# SignalOutput.net
KiCad netlist of a schematic drawn in Altium Designer
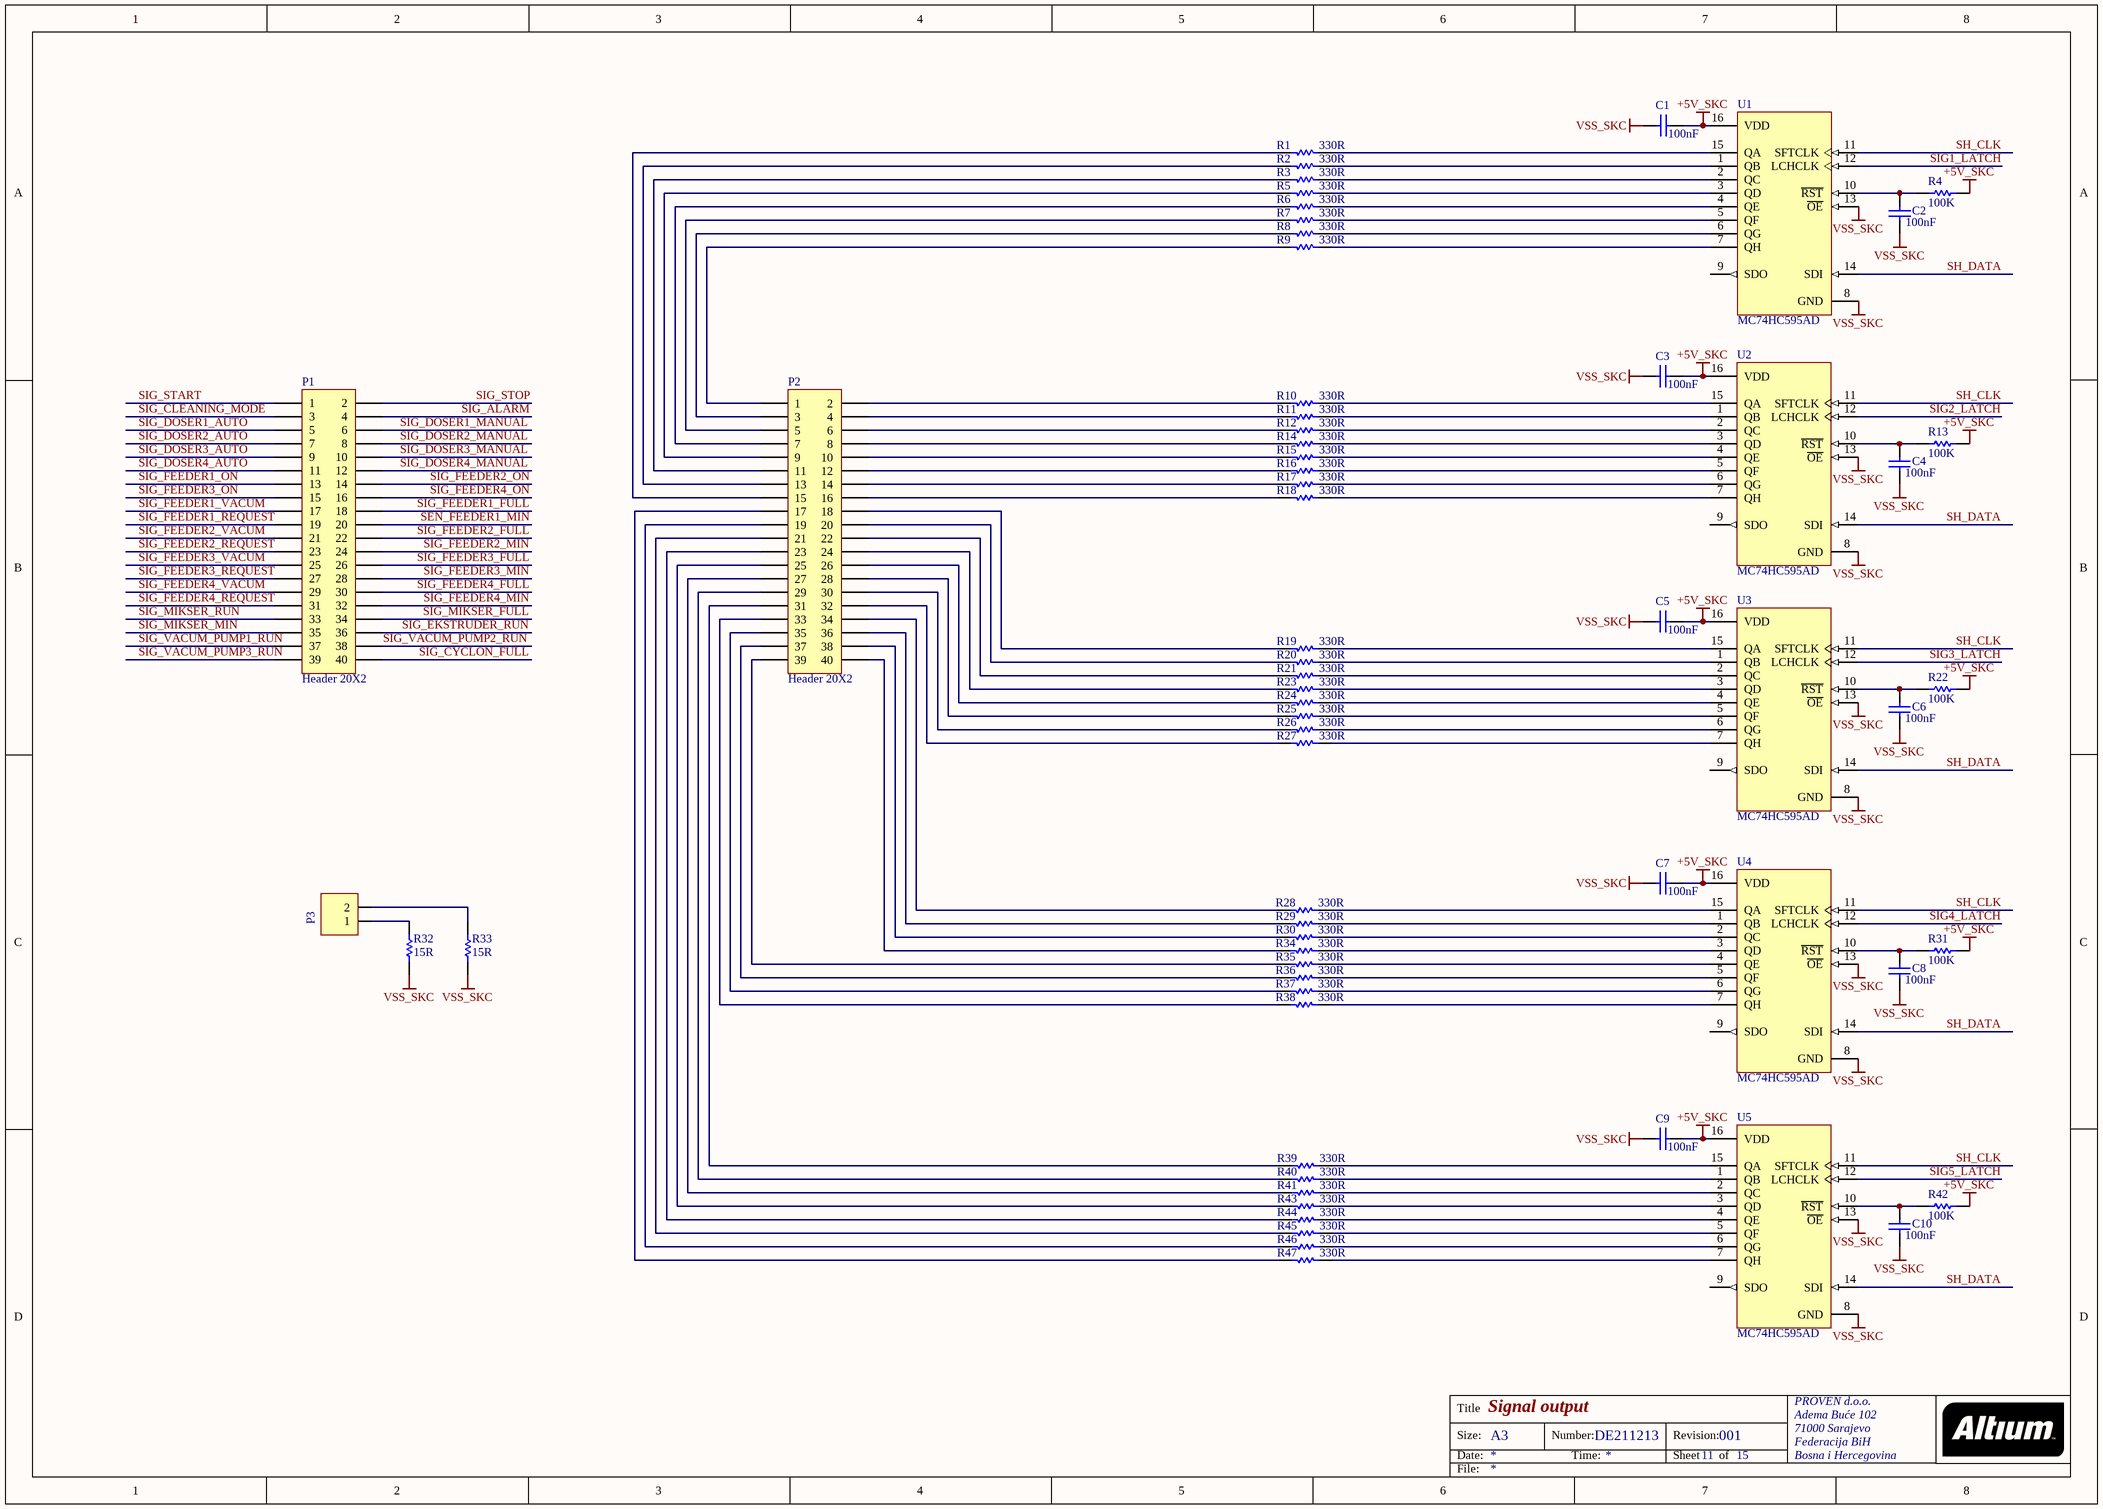
[diagram p0: SignalOutput.SchDoc]

(export (version "E")
  (design (tool "Eeschema 10.0.6"))
  (components
    (comp (ref "C1")
      (value "100nF")
      (footprint "1206")
      (description "Ceramic Chip Capacitor - Standard")
      (fields (field (name "PUBLISHER") "Altium Limited"))
      (libsource (lib "KEMET Chip Capacitor") (part "C1206"))
    )
    (comp (ref "C2")
      (value "100nF")
      (footprint "1206")
      (description "Ceramic Chip Capacitor - Standard")
      (fields (field (name "PUBLISHER") "Altium Limited"))
      (libsource (lib "KEMET Chip Capacitor") (part "C1206"))
    )
    (comp (ref "C3")
      (value "100nF")
      (footprint "1206")
      (description "Ceramic Chip Capacitor - Standard")
      (fields (field (name "PUBLISHER") "Altium Limited"))
      (libsource (lib "KEMET Chip Capacitor") (part "C1206"))
    )
    (comp (ref "C4")
      (value "100nF")
      (footprint "1206")
      (description "Ceramic Chip Capacitor - Standard")
      (fields (field (name "PUBLISHER") "Altium Limited"))
      (libsource (lib "KEMET Chip Capacitor") (part "C1206"))
    )
    (comp (ref "C5")
      (value "100nF")
      (footprint "1206")
      (description "Ceramic Chip Capacitor - Standard")
      (fields (field (name "PUBLISHER") "Altium Limited"))
      (libsource (lib "KEMET Chip Capacitor") (part "C1206"))
    )
    (comp (ref "C6")
      (value "100nF")
      (footprint "1206")
      (description "Ceramic Chip Capacitor - Standard")
      (fields (field (name "PUBLISHER") "Altium Limited"))
      (libsource (lib "KEMET Chip Capacitor") (part "C1206"))
    )
    (comp (ref "C7")
      (value "100nF")
      (footprint "1206")
      (description "Ceramic Chip Capacitor - Standard")
      (fields (field (name "PUBLISHER") "Altium Limited"))
      (libsource (lib "KEMET Chip Capacitor") (part "C1206"))
    )
    (comp (ref "C8")
      (value "100nF")
      (footprint "1206")
      (description "Ceramic Chip Capacitor - Standard")
      (fields (field (name "PUBLISHER") "Altium Limited"))
      (libsource (lib "KEMET Chip Capacitor") (part "C1206"))
    )
    (comp (ref "C9")
      (value "100nF")
      (footprint "1206")
      (description "Ceramic Chip Capacitor - Standard")
      (fields (field (name "PUBLISHER") "Altium Limited"))
      (libsource (lib "KEMET Chip Capacitor") (part "C1206"))
    )
    (comp (ref "C10")
      (value "100nF")
      (footprint "1206")
      (description "Ceramic Chip Capacitor - Standard")
      (fields (field (name "PUBLISHER") "Altium Limited"))
      (libsource (lib "KEMET Chip Capacitor") (part "C1206"))
    )
    (comp (ref "P1")
      (value "Header 20X2")
      (footprint "HDR2X20")
      (description "Header, 20-Pin, Dual row")
      (fields (field (name "PUBLISHER") "Altium Limited"))
      (libsource (lib "Miscellaneous Connectors") (part "Header 20X2"))
    )
    (comp (ref "P2")
      (value "Header 20X2")
      (footprint "HDR2X20")
      (description "Header, 20-Pin, Dual row")
      (fields (field (name "PUBLISHER") "Altium Limited"))
      (libsource (lib "Miscellaneous Connectors") (part "Header 20X2"))
    )
    (comp (ref "P3")
      (value "~")
      (footprint "TERMINAL BLOK 2")
      (description "Terminal blok 2")
      (libsource (lib "TERMINAL_CONNECOR_2") (part "Terminal blok 2 pina"))
    )
    (comp (ref "R1")
      (value "330R")
      (footprint "ERA-0805")
      (fields (field (name "PUBLISHER") "Altium Limited"))
      (libsource (lib "Panasonic Resistor") (part "ERA6Y"))
    )
    (comp (ref "R2")
      (value "330R")
      (footprint "ERA-0805")
      (fields (field (name "PUBLISHER") "Altium Limited"))
      (libsource (lib "Panasonic Resistor") (part "ERA6Y"))
    )
    (comp (ref "R3")
      (value "330R")
      (footprint "ERA-0805")
      (fields (field (name "PUBLISHER") "Altium Limited"))
      (libsource (lib "Panasonic Resistor") (part "ERA6Y"))
    )
    (comp (ref "R4")
      (value "100K")
      (footprint "ERA-0603")
      (fields (field (name "PUBLISHER") "Altium Limited"))
      (libsource (lib "Panasonic Resistor") (part "ERA3Y"))
    )
    (comp (ref "R5")
      (value "330R")
      (footprint "ERA-0805")
      (fields (field (name "PUBLISHER") "Altium Limited"))
      (libsource (lib "Panasonic Resistor") (part "ERA6Y"))
    )
    (comp (ref "R6")
      (value "330R")
      (footprint "ERA-0805")
      (fields (field (name "PUBLISHER") "Altium Limited"))
      (libsource (lib "Panasonic Resistor") (part "ERA6Y"))
    )
    (comp (ref "R7")
      (value "330R")
      (footprint "ERA-0805")
      (fields (field (name "PUBLISHER") "Altium Limited"))
      (libsource (lib "Panasonic Resistor") (part "ERA6Y"))
    )
    (comp (ref "R8")
      (value "330R")
      (footprint "ERA-0805")
      (fields (field (name "PUBLISHER") "Altium Limited"))
      (libsource (lib "Panasonic Resistor") (part "ERA6Y"))
    )
    (comp (ref "R9")
      (value "330R")
      (footprint "ERA-0805")
      (fields (field (name "PUBLISHER") "Altium Limited"))
      (libsource (lib "Panasonic Resistor") (part "ERA6Y"))
    )
    (comp (ref "R10")
      (value "330R")
      (footprint "ERA-0805")
      (fields (field (name "PUBLISHER") "Altium Limited"))
      (libsource (lib "Panasonic Resistor") (part "ERA6Y"))
    )
    (comp (ref "R11")
      (value "330R")
      (footprint "ERA-0805")
      (fields (field (name "PUBLISHER") "Altium Limited"))
      (libsource (lib "Panasonic Resistor") (part "ERA6Y"))
    )
    (comp (ref "R12")
      (value "330R")
      (footprint "ERA-0805")
      (fields (field (name "PUBLISHER") "Altium Limited"))
      (libsource (lib "Panasonic Resistor") (part "ERA6Y"))
    )
    (comp (ref "R13")
      (value "100K")
      (footprint "ERA-0603")
      (fields (field (name "PUBLISHER") "Altium Limited"))
      (libsource (lib "Panasonic Resistor") (part "ERA3Y"))
    )
    (comp (ref "R14")
      (value "330R")
      (footprint "ERA-0805")
      (fields (field (name "PUBLISHER") "Altium Limited"))
      (libsource (lib "Panasonic Resistor") (part "ERA6Y"))
    )
    (comp (ref "R15")
      (value "330R")
      (footprint "ERA-0805")
      (fields (field (name "PUBLISHER") "Altium Limited"))
      (libsource (lib "Panasonic Resistor") (part "ERA6Y"))
    )
    (comp (ref "R16")
      (value "330R")
      (footprint "ERA-0805")
      (fields (field (name "PUBLISHER") "Altium Limited"))
      (libsource (lib "Panasonic Resistor") (part "ERA6Y"))
    )
    (comp (ref "R17")
      (value "330R")
      (footprint "ERA-0805")
      (fields (field (name "PUBLISHER") "Altium Limited"))
      (libsource (lib "Panasonic Resistor") (part "ERA6Y"))
    )
    (comp (ref "R18")
      (value "330R")
      (footprint "ERA-0805")
      (fields (field (name "PUBLISHER") "Altium Limited"))
      (libsource (lib "Panasonic Resistor") (part "ERA6Y"))
    )
    (comp (ref "R19")
      (value "330R")
      (footprint "ERA-0805")
      (fields (field (name "PUBLISHER") "Altium Limited"))
      (libsource (lib "Panasonic Resistor") (part "ERA6Y"))
    )
    (comp (ref "R20")
      (value "330R")
      (footprint "ERA-0805")
      (fields (field (name "PUBLISHER") "Altium Limited"))
      (libsource (lib "Panasonic Resistor") (part "ERA6Y"))
    )
    (comp (ref "R21")
      (value "330R")
      (footprint "ERA-0805")
      (fields (field (name "PUBLISHER") "Altium Limited"))
      (libsource (lib "Panasonic Resistor") (part "ERA6Y"))
    )
    (comp (ref "R22")
      (value "100K")
      (footprint "ERA-0603")
      (fields (field (name "PUBLISHER") "Altium Limited"))
      (libsource (lib "Panasonic Resistor") (part "ERA3Y"))
    )
    (comp (ref "R23")
      (value "330R")
      (footprint "ERA-0805")
      (fields (field (name "PUBLISHER") "Altium Limited"))
      (libsource (lib "Panasonic Resistor") (part "ERA6Y"))
    )
    (comp (ref "R24")
      (value "330R")
      (footprint "ERA-0805")
      (fields (field (name "PUBLISHER") "Altium Limited"))
      (libsource (lib "Panasonic Resistor") (part "ERA6Y"))
    )
    (comp (ref "R25")
      (value "330R")
      (footprint "ERA-0805")
      (fields (field (name "PUBLISHER") "Altium Limited"))
      (libsource (lib "Panasonic Resistor") (part "ERA6Y"))
    )
    (comp (ref "R26")
      (value "330R")
      (footprint "ERA-0805")
      (fields (field (name "PUBLISHER") "Altium Limited"))
      (libsource (lib "Panasonic Resistor") (part "ERA6Y"))
    )
    (comp (ref "R27")
      (value "330R")
      (footprint "ERA-0805")
      (fields (field (name "PUBLISHER") "Altium Limited"))
      (libsource (lib "Panasonic Resistor") (part "ERA6Y"))
    )
    (comp (ref "R28")
      (value "330R")
      (footprint "ERA-0805")
      (fields (field (name "PUBLISHER") "Altium Limited"))
      (libsource (lib "Panasonic Resistor") (part "ERA6Y"))
    )
    (comp (ref "R29")
      (value "330R")
      (footprint "ERA-0805")
      (fields (field (name "PUBLISHER") "Altium Limited"))
      (libsource (lib "Panasonic Resistor") (part "ERA6Y"))
    )
    (comp (ref "R30")
      (value "330R")
      (footprint "ERA-0805")
      (fields (field (name "PUBLISHER") "Altium Limited"))
      (libsource (lib "Panasonic Resistor") (part "ERA6Y"))
    )
    (comp (ref "R31")
      (value "100K")
      (footprint "ERA-0603")
      (fields (field (name "PUBLISHER") "Altium Limited"))
      (libsource (lib "Panasonic Resistor") (part "ERA3Y"))
    )
    (comp (ref "R32")
      (value "15R")
      (footprint "RD6.35x2.3")
      (description "Carbon Film Resistor, 1 Ohm to 3.3M Ohm Range, 5% Tolerance, 0.25 W")
      (fields (field (name "PUBLISHER") "Altium Limited"))
      (libsource (lib "Panasonic Resistor") (part "ERD25T"))
    )
    (comp (ref "R33")
      (value "15R")
      (footprint "RD6.35x2.3")
      (description "Carbon Film Resistor, 1 Ohm to 3.3M Ohm Range, 5% Tolerance, 0.25 W")
      (fields (field (name "PUBLISHER") "Altium Limited"))
      (libsource (lib "Panasonic Resistor") (part "ERD25T"))
    )
    (comp (ref "R34")
      (value "330R")
      (footprint "ERA-0805")
      (fields (field (name "PUBLISHER") "Altium Limited"))
      (libsource (lib "Panasonic Resistor") (part "ERA6Y"))
    )
    (comp (ref "R35")
      (value "330R")
      (footprint "ERA-0805")
      (fields (field (name "PUBLISHER") "Altium Limited"))
      (libsource (lib "Panasonic Resistor") (part "ERA6Y"))
    )
    (comp (ref "R36")
      (value "330R")
      (footprint "ERA-0805")
      (fields (field (name "PUBLISHER") "Altium Limited"))
      (libsource (lib "Panasonic Resistor") (part "ERA6Y"))
    )
    (comp (ref "R37")
      (value "330R")
      (footprint "ERA-0805")
      (fields (field (name "PUBLISHER") "Altium Limited"))
      (libsource (lib "Panasonic Resistor") (part "ERA6Y"))
    )
    (comp (ref "R38")
      (value "330R")
      (footprint "ERA-0805")
      (fields (field (name "PUBLISHER") "Altium Limited"))
      (libsource (lib "Panasonic Resistor") (part "ERA6Y"))
    )
    (comp (ref "R39")
      (value "330R")
      (footprint "ERA-0805")
      (fields (field (name "PUBLISHER") "Altium Limited"))
      (libsource (lib "Panasonic Resistor") (part "ERA6Y"))
    )
    (comp (ref "R40")
      (value "330R")
      (footprint "ERA-0805")
      (fields (field (name "PUBLISHER") "Altium Limited"))
      (libsource (lib "Panasonic Resistor") (part "ERA6Y"))
    )
    (comp (ref "R41")
      (value "330R")
      (footprint "ERA-0805")
      (fields (field (name "PUBLISHER") "Altium Limited"))
      (libsource (lib "Panasonic Resistor") (part "ERA6Y"))
    )
    (comp (ref "R42")
      (value "100K")
      (footprint "ERA-0603")
      (fields (field (name "PUBLISHER") "Altium Limited"))
      (libsource (lib "Panasonic Resistor") (part "ERA3Y"))
    )
    (comp (ref "R43")
      (value "330R")
      (footprint "ERA-0805")
      (fields (field (name "PUBLISHER") "Altium Limited"))
      (libsource (lib "Panasonic Resistor") (part "ERA6Y"))
    )
    (comp (ref "R44")
      (value "330R")
      (footprint "ERA-0805")
      (fields (field (name "PUBLISHER") "Altium Limited"))
      (libsource (lib "Panasonic Resistor") (part "ERA6Y"))
    )
    (comp (ref "R45")
      (value "330R")
      (footprint "ERA-0805")
      (fields (field (name "PUBLISHER") "Altium Limited"))
      (libsource (lib "Panasonic Resistor") (part "ERA6Y"))
    )
    (comp (ref "R46")
      (value "330R")
      (footprint "ERA-0805")
      (fields (field (name "PUBLISHER") "Altium Limited"))
      (libsource (lib "Panasonic Resistor") (part "ERA6Y"))
    )
    (comp (ref "R47")
      (value "330R")
      (footprint "ERA-0805")
      (fields (field (name "PUBLISHER") "Altium Limited"))
      (libsource (lib "Panasonic Resistor") (part "ERA6Y"))
    )
    (comp (ref "U1")
      (value "MC74HC595AD")
      (footprint "751B-05_N")
      (description "8-Bit Serial-Input/Serial or Prallel-Output Shift Register with Latched 3-State Outputs")
      (fields (field (name "PUBLISHER") "Altium Limited"))
      (libsource (lib "ON Semi Logic Register") (part "MC74HC595AD"))
    )
    (comp (ref "U2")
      (value "MC74HC595AD")
      (footprint "751B-05_N")
      (description "8-Bit Serial-Input/Serial or Prallel-Output Shift Register with Latched 3-State Outputs")
      (fields (field (name "PUBLISHER") "Altium Limited"))
      (libsource (lib "ON Semi Logic Register") (part "MC74HC595AD"))
    )
    (comp (ref "U3")
      (value "MC74HC595AD")
      (footprint "751B-05_N")
      (description "8-Bit Serial-Input/Serial or Prallel-Output Shift Register with Latched 3-State Outputs")
      (fields (field (name "PUBLISHER") "Altium Limited"))
      (libsource (lib "ON Semi Logic Register") (part "MC74HC595AD"))
    )
    (comp (ref "U4")
      (value "MC74HC595AD")
      (footprint "751B-05_N")
      (description "8-Bit Serial-Input/Serial or Prallel-Output Shift Register with Latched 3-State Outputs")
      (fields (field (name "PUBLISHER") "Altium Limited"))
      (libsource (lib "ON Semi Logic Register") (part "MC74HC595AD"))
    )
    (comp (ref "U5")
      (value "MC74HC595AD")
      (footprint "751B-05_N")
      (description "8-Bit Serial-Input/Serial or Prallel-Output Shift Register with Latched 3-State Outputs")
      (fields (field (name "PUBLISHER") "Altium Limited"))
      (libsource (lib "ON Semi Logic Register") (part "MC74HC595AD"))
    )
  )
  (nets
    (net (code "1") (name "+5V_SKC") (class "Default")
      (node (ref "C1") (pin "1") (pinfunction "1_1") (pintype "passive"))
      (node (ref "C3") (pin "1") (pinfunction "1_1") (pintype "passive"))
      (node (ref "C5") (pin "1") (pinfunction "1_1") (pintype "passive"))
      (node (ref "C7") (pin "1") (pinfunction "1_1") (pintype "passive"))
      (node (ref "C9") (pin "1") (pinfunction "1_1") (pintype "passive"))
      (node (ref "R13") (pin "2") (pinfunction "2_2") (pintype "passive"))
      (node (ref "R22") (pin "2") (pinfunction "2_2") (pintype "passive"))
      (node (ref "R31") (pin "2") (pinfunction "2_2") (pintype "passive"))
      (node (ref "R4") (pin "2") (pinfunction "2_2") (pintype "passive"))
      (node (ref "R42") (pin "2") (pinfunction "2_2") (pintype "passive"))
      (node (ref "U1") (pin "16") (pinfunction "VDD_16") (pintype "power_in"))
      (node (ref "U2") (pin "16") (pinfunction "VDD_16") (pintype "power_in"))
      (node (ref "U3") (pin "16") (pinfunction "VDD_16") (pintype "power_in"))
      (node (ref "U4") (pin "16") (pinfunction "VDD_16") (pintype "power_in"))
      (node (ref "U5") (pin "16") (pinfunction "VDD_16") (pintype "power_in"))
    )
    (net (code "2") (name "/SEN_FEEDER1_MIN") (class "Default")
      (node (ref "P1") (pin "20") (pinfunction "20_20") (pintype "passive"))
    )
    (net (code "3") (name "/SH_CLK") (class "Default")
      (node (ref "U1") (pin "11") (pinfunction "SFTCLK_11") (pintype "input"))
      (node (ref "U2") (pin "11") (pinfunction "SFTCLK_11") (pintype "input"))
      (node (ref "U3") (pin "11") (pinfunction "SFTCLK_11") (pintype "input"))
      (node (ref "U4") (pin "11") (pinfunction "SFTCLK_11") (pintype "input"))
      (node (ref "U5") (pin "11") (pinfunction "SFTCLK_11") (pintype "input"))
    )
    (net (code "4") (name "/SH_DATA") (class "Default")
      (node (ref "U1") (pin "14") (pinfunction "SDI_14") (pintype "input"))
      (node (ref "U2") (pin "14") (pinfunction "SDI_14") (pintype "input"))
      (node (ref "U3") (pin "14") (pinfunction "SDI_14") (pintype "input"))
      (node (ref "U4") (pin "14") (pinfunction "SDI_14") (pintype "input"))
      (node (ref "U5") (pin "14") (pinfunction "SDI_14") (pintype "input"))
    )
    (net (code "5") (name "/SIG1_LATCH") (class "Default")
      (node (ref "U1") (pin "12") (pinfunction "LCHCLK_12") (pintype "input"))
    )
    (net (code "6") (name "/SIG2_LATCH") (class "Default")
      (node (ref "U2") (pin "12") (pinfunction "LCHCLK_12") (pintype "input"))
    )
    (net (code "7") (name "/SIG3_LATCH") (class "Default")
      (node (ref "U3") (pin "12") (pinfunction "LCHCLK_12") (pintype "input"))
    )
    (net (code "8") (name "/SIG4_LATCH") (class "Default")
      (node (ref "U4") (pin "12") (pinfunction "LCHCLK_12") (pintype "input"))
    )
    (net (code "9") (name "/SIG5_LATCH") (class "Default")
      (node (ref "U5") (pin "12") (pinfunction "LCHCLK_12") (pintype "input"))
    )
    (net (code "10") (name "/SIG_ALARM") (class "Default")
      (node (ref "P1") (pin "4") (pinfunction "4_4") (pintype "passive"))
    )
    (net (code "11") (name "/SIG_CLEANING_MODE") (class "Default")
      (node (ref "P1") (pin "3") (pinfunction "3_3") (pintype "passive"))
    )
    (net (code "12") (name "/SIG_CYCLON_FULL") (class "Default")
      (node (ref "P1") (pin "40") (pinfunction "40_40") (pintype "passive"))
    )
    (net (code "13") (name "/SIG_DOSER1_AUTO") (class "Default")
      (node (ref "P1") (pin "5") (pinfunction "5_5") (pintype "passive"))
    )
    (net (code "14") (name "/SIG_DOSER1_MANUAL") (class "Default")
      (node (ref "P1") (pin "6") (pinfunction "6_6") (pintype "passive"))
    )
    (net (code "15") (name "/SIG_DOSER2_AUTO") (class "Default")
      (node (ref "P1") (pin "7") (pinfunction "7_7") (pintype "passive"))
    )
    (net (code "16") (name "/SIG_DOSER2_MANUAL") (class "Default")
      (node (ref "P1") (pin "8") (pinfunction "8_8") (pintype "passive"))
    )
    (net (code "17") (name "/SIG_DOSER3_AUTO") (class "Default")
      (node (ref "P1") (pin "9") (pinfunction "9_9") (pintype "passive"))
    )
    (net (code "18") (name "/SIG_DOSER3_MANUAL") (class "Default")
      (node (ref "P1") (pin "10") (pinfunction "10_10") (pintype "passive"))
    )
    (net (code "19") (name "/SIG_DOSER4_AUTO") (class "Default")
      (node (ref "P1") (pin "11") (pinfunction "11_11") (pintype "passive"))
    )
    (net (code "20") (name "/SIG_DOSER4_MANUAL") (class "Default")
      (node (ref "P1") (pin "12") (pinfunction "12_12") (pintype "passive"))
    )
    (net (code "21") (name "/SIG_EKSTRUDER_RUN") (class "Default")
      (node (ref "P1") (pin "36") (pinfunction "36_36") (pintype "passive"))
    )
    (net (code "22") (name "/SIG_FEEDER1_FULL") (class "Default")
      (node (ref "P1") (pin "18") (pinfunction "18_18") (pintype "passive"))
    )
    (net (code "23") (name "/SIG_FEEDER1_ON") (class "Default")
      (node (ref "P1") (pin "13") (pinfunction "13_13") (pintype "passive"))
    )
    (net (code "24") (name "/SIG_FEEDER1_REQUEST") (class "Default")
      (node (ref "P1") (pin "19") (pinfunction "19_19") (pintype "passive"))
    )
    (net (code "25") (name "/SIG_FEEDER1_VACUM") (class "Default")
      (node (ref "P1") (pin "17") (pinfunction "17_17") (pintype "passive"))
    )
    (net (code "26") (name "/SIG_FEEDER2_FULL") (class "Default")
      (node (ref "P1") (pin "22") (pinfunction "22_22") (pintype "passive"))
    )
    (net (code "27") (name "/SIG_FEEDER2_MIN") (class "Default")
      (node (ref "P1") (pin "24") (pinfunction "24_24") (pintype "passive"))
    )
    (net (code "28") (name "/SIG_FEEDER2_ON") (class "Default")
      (node (ref "P1") (pin "14") (pinfunction "14_14") (pintype "passive"))
    )
    (net (code "29") (name "/SIG_FEEDER2_REQUEST") (class "Default")
      (node (ref "P1") (pin "23") (pinfunction "23_23") (pintype "passive"))
    )
    (net (code "30") (name "/SIG_FEEDER2_VACUM") (class "Default")
      (node (ref "P1") (pin "21") (pinfunction "21_21") (pintype "passive"))
    )
    (net (code "31") (name "/SIG_FEEDER3_FULL") (class "Default")
      (node (ref "P1") (pin "26") (pinfunction "26_26") (pintype "passive"))
    )
    (net (code "32") (name "/SIG_FEEDER3_MIN") (class "Default")
      (node (ref "P1") (pin "28") (pinfunction "28_28") (pintype "passive"))
    )
    (net (code "33") (name "/SIG_FEEDER3_ON") (class "Default")
      (node (ref "P1") (pin "15") (pinfunction "15_15") (pintype "passive"))
    )
    (net (code "34") (name "/SIG_FEEDER3_REQUEST") (class "Default")
      (node (ref "P1") (pin "27") (pinfunction "27_27") (pintype "passive"))
    )
    (net (code "35") (name "/SIG_FEEDER3_VACUM") (class "Default")
      (node (ref "P1") (pin "25") (pinfunction "25_25") (pintype "passive"))
    )
    (net (code "36") (name "/SIG_FEEDER4_FULL") (class "Default")
      (node (ref "P1") (pin "30") (pinfunction "30_30") (pintype "passive"))
    )
    (net (code "37") (name "/SIG_FEEDER4_MIN") (class "Default")
      (node (ref "P1") (pin "32") (pinfunction "32_32") (pintype "passive"))
    )
    (net (code "38") (name "/SIG_FEEDER4_ON") (class "Default")
      (node (ref "P1") (pin "16") (pinfunction "16_16") (pintype "passive"))
    )
    (net (code "39") (name "/SIG_FEEDER4_REQUEST") (class "Default")
      (node (ref "P1") (pin "31") (pinfunction "31_31") (pintype "passive"))
    )
    (net (code "40") (name "/SIG_FEEDER4_VACUM") (class "Default")
      (node (ref "P1") (pin "29") (pinfunction "29_29") (pintype "passive"))
    )
    (net (code "41") (name "/SIG_MIKSER_FULL") (class "Default")
      (node (ref "P1") (pin "34") (pinfunction "34_34") (pintype "passive"))
    )
    (net (code "42") (name "/SIG_MIKSER_MIN") (class "Default")
      (node (ref "P1") (pin "35") (pinfunction "35_35") (pintype "passive"))
    )
    (net (code "43") (name "/SIG_MIKSER_RUN") (class "Default")
      (node (ref "P1") (pin "33") (pinfunction "33_33") (pintype "passive"))
    )
    (net (code "44") (name "/SIG_START") (class "Default")
      (node (ref "P1") (pin "1") (pinfunction "1_1") (pintype "passive"))
    )
    (net (code "45") (name "/SIG_STOP") (class "Default")
      (node (ref "P1") (pin "2") (pinfunction "2_2") (pintype "passive"))
    )
    (net (code "46") (name "/SIG_VACUM_PUMP1_RUN") (class "Default")
      (node (ref "P1") (pin "37") (pinfunction "37_37") (pintype "passive"))
    )
    (net (code "47") (name "/SIG_VACUM_PUMP2_RUN") (class "Default")
      (node (ref "P1") (pin "38") (pinfunction "38_38") (pintype "passive"))
    )
    (net (code "48") (name "/SIG_VACUM_PUMP3_RUN") (class "Default")
      (node (ref "P1") (pin "39") (pinfunction "39_39") (pintype "passive"))
    )
    (net (code "49") (name "Net-(P2-Pad1)") (class "Default")
      (node (ref "P2") (pin "1") (pinfunction "1_1") (pintype "passive"))
      (node (ref "R9") (pin "1") (pinfunction "1_1") (pintype "passive"))
    )
    (net (code "50") (name "Net-(P2-Pad2)") (class "Default")
      (node (ref "P2") (pin "2") (pinfunction "2_2") (pintype "passive"))
      (node (ref "R10") (pin "1") (pinfunction "1_1") (pintype "passive"))
    )
    (net (code "51") (name "Net-(P2-Pad3)") (class "Default")
      (node (ref "P2") (pin "3") (pinfunction "3_3") (pintype "passive"))
      (node (ref "R8") (pin "1") (pinfunction "1_1") (pintype "passive"))
    )
    (net (code "52") (name "Net-(P2-Pad4)") (class "Default")
      (node (ref "P2") (pin "4") (pinfunction "4_4") (pintype "passive"))
      (node (ref "R11") (pin "1") (pinfunction "1_1") (pintype "passive"))
    )
    (net (code "53") (name "Net-(P2-Pad5)") (class "Default")
      (node (ref "P2") (pin "5") (pinfunction "5_5") (pintype "passive"))
      (node (ref "R7") (pin "1") (pinfunction "1_1") (pintype "passive"))
    )
    (net (code "54") (name "Net-(P2-Pad6)") (class "Default")
      (node (ref "P2") (pin "6") (pinfunction "6_6") (pintype "passive"))
      (node (ref "R12") (pin "1") (pinfunction "1_1") (pintype "passive"))
    )
    (net (code "55") (name "Net-(P2-Pad7)") (class "Default")
      (node (ref "P2") (pin "7") (pinfunction "7_7") (pintype "passive"))
      (node (ref "R6") (pin "1") (pinfunction "1_1") (pintype "passive"))
    )
    (net (code "56") (name "Net-(P2-Pad8)") (class "Default")
      (node (ref "P2") (pin "8") (pinfunction "8_8") (pintype "passive"))
      (node (ref "R14") (pin "1") (pinfunction "1_1") (pintype "passive"))
    )
    (net (code "57") (name "Net-(P2-Pad9)") (class "Default")
      (node (ref "P2") (pin "9") (pinfunction "9_9") (pintype "passive"))
      (node (ref "R5") (pin "1") (pinfunction "1_1") (pintype "passive"))
    )
    (net (code "58") (name "Net-(P2-Pad10)") (class "Default")
      (node (ref "P2") (pin "10") (pinfunction "10_10") (pintype "passive"))
      (node (ref "R15") (pin "1") (pinfunction "1_1") (pintype "passive"))
    )
    (net (code "59") (name "Net-(P2-Pad11)") (class "Default")
      (node (ref "P2") (pin "11") (pinfunction "11_11") (pintype "passive"))
      (node (ref "R3") (pin "1") (pinfunction "1_1") (pintype "passive"))
    )
    (net (code "60") (name "Net-(P2-Pad12)") (class "Default")
      (node (ref "P2") (pin "12") (pinfunction "12_12") (pintype "passive"))
      (node (ref "R16") (pin "1") (pinfunction "1_1") (pintype "passive"))
    )
    (net (code "61") (name "Net-(P2-Pad13)") (class "Default")
      (node (ref "P2") (pin "13") (pinfunction "13_13") (pintype "passive"))
      (node (ref "R2") (pin "1") (pinfunction "1_1") (pintype "passive"))
    )
    (net (code "62") (name "Net-(P2-Pad14)") (class "Default")
      (node (ref "P2") (pin "14") (pinfunction "14_14") (pintype "passive"))
      (node (ref "R17") (pin "1") (pinfunction "1_1") (pintype "passive"))
    )
    (net (code "63") (name "Net-(P2-Pad15)") (class "Default")
      (node (ref "P2") (pin "15") (pinfunction "15_15") (pintype "passive"))
      (node (ref "R1") (pin "1") (pinfunction "1_1") (pintype "passive"))
    )
    (net (code "64") (name "Net-(P2-Pad16)") (class "Default")
      (node (ref "P2") (pin "16") (pinfunction "16_16") (pintype "passive"))
      (node (ref "R18") (pin "1") (pinfunction "1_1") (pintype "passive"))
    )
    (net (code "65") (name "Net-(P2-Pad17)") (class "Default")
      (node (ref "P2") (pin "17") (pinfunction "17_17") (pintype "passive"))
      (node (ref "R47") (pin "1") (pinfunction "1_1") (pintype "passive"))
    )
    (net (code "66") (name "Net-(P2-Pad18)") (class "Default")
      (node (ref "P2") (pin "18") (pinfunction "18_18") (pintype "passive"))
      (node (ref "R19") (pin "1") (pinfunction "1_1") (pintype "passive"))
    )
    (net (code "67") (name "Net-(P2-Pad19)") (class "Default")
      (node (ref "P2") (pin "19") (pinfunction "19_19") (pintype "passive"))
      (node (ref "R46") (pin "1") (pinfunction "1_1") (pintype "passive"))
    )
    (net (code "68") (name "Net-(P2-Pad20)") (class "Default")
      (node (ref "P2") (pin "20") (pinfunction "20_20") (pintype "passive"))
      (node (ref "R20") (pin "1") (pinfunction "1_1") (pintype "passive"))
    )
    (net (code "69") (name "Net-(P2-Pad21)") (class "Default")
      (node (ref "P2") (pin "21") (pinfunction "21_21") (pintype "passive"))
      (node (ref "R45") (pin "1") (pinfunction "1_1") (pintype "passive"))
    )
    (net (code "70") (name "Net-(P2-Pad22)") (class "Default")
      (node (ref "P2") (pin "22") (pinfunction "22_22") (pintype "passive"))
      (node (ref "R21") (pin "1") (pinfunction "1_1") (pintype "passive"))
    )
    (net (code "71") (name "Net-(P2-Pad23)") (class "Default")
      (node (ref "P2") (pin "23") (pinfunction "23_23") (pintype "passive"))
      (node (ref "R44") (pin "1") (pinfunction "1_1") (pintype "passive"))
    )
    (net (code "72") (name "Net-(P2-Pad24)") (class "Default")
      (node (ref "P2") (pin "24") (pinfunction "24_24") (pintype "passive"))
      (node (ref "R23") (pin "1") (pinfunction "1_1") (pintype "passive"))
    )
    (net (code "73") (name "Net-(P2-Pad25)") (class "Default")
      (node (ref "P2") (pin "25") (pinfunction "25_25") (pintype "passive"))
      (node (ref "R43") (pin "1") (pinfunction "1_1") (pintype "passive"))
    )
    (net (code "74") (name "Net-(P2-Pad26)") (class "Default")
      (node (ref "P2") (pin "26") (pinfunction "26_26") (pintype "passive"))
      (node (ref "R24") (pin "1") (pinfunction "1_1") (pintype "passive"))
    )
    (net (code "75") (name "Net-(P2-Pad27)") (class "Default")
      (node (ref "P2") (pin "27") (pinfunction "27_27") (pintype "passive"))
      (node (ref "R41") (pin "1") (pinfunction "1_1") (pintype "passive"))
    )
    (net (code "76") (name "Net-(P2-Pad28)") (class "Default")
      (node (ref "P2") (pin "28") (pinfunction "28_28") (pintype "passive"))
      (node (ref "R25") (pin "1") (pinfunction "1_1") (pintype "passive"))
    )
    (net (code "77") (name "Net-(P2-Pad29)") (class "Default")
      (node (ref "P2") (pin "29") (pinfunction "29_29") (pintype "passive"))
      (node (ref "R40") (pin "1") (pinfunction "1_1") (pintype "passive"))
    )
    (net (code "78") (name "Net-(P2-Pad30)") (class "Default")
      (node (ref "P2") (pin "30") (pinfunction "30_30") (pintype "passive"))
      (node (ref "R26") (pin "1") (pinfunction "1_1") (pintype "passive"))
    )
    (net (code "79") (name "Net-(P2-Pad31)") (class "Default")
      (node (ref "P2") (pin "31") (pinfunction "31_31") (pintype "passive"))
      (node (ref "R39") (pin "1") (pinfunction "1_1") (pintype "passive"))
    )
    (net (code "80") (name "Net-(P2-Pad32)") (class "Default")
      (node (ref "P2") (pin "32") (pinfunction "32_32") (pintype "passive"))
      (node (ref "R27") (pin "1") (pinfunction "1_1") (pintype "passive"))
    )
    (net (code "81") (name "Net-(P2-Pad33)") (class "Default")
      (node (ref "P2") (pin "33") (pinfunction "33_33") (pintype "passive"))
      (node (ref "R38") (pin "1") (pinfunction "1_1") (pintype "passive"))
    )
    (net (code "82") (name "Net-(P2-Pad34)") (class "Default")
      (node (ref "P2") (pin "34") (pinfunction "34_34") (pintype "passive"))
      (node (ref "R28") (pin "1") (pinfunction "1_1") (pintype "passive"))
    )
    (net (code "83") (name "Net-(P2-Pad35)") (class "Default")
      (node (ref "P2") (pin "35") (pinfunction "35_35") (pintype "passive"))
      (node (ref "R37") (pin "1") (pinfunction "1_1") (pintype "passive"))
    )
    (net (code "84") (name "Net-(P2-Pad36)") (class "Default")
      (node (ref "P2") (pin "36") (pinfunction "36_36") (pintype "passive"))
      (node (ref "R29") (pin "1") (pinfunction "1_1") (pintype "passive"))
    )
    (net (code "85") (name "Net-(P2-Pad37)") (class "Default")
      (node (ref "P2") (pin "37") (pinfunction "37_37") (pintype "passive"))
      (node (ref "R36") (pin "1") (pinfunction "1_1") (pintype "passive"))
    )
    (net (code "86") (name "Net-(P2-Pad38)") (class "Default")
      (node (ref "P2") (pin "38") (pinfunction "38_38") (pintype "passive"))
      (node (ref "R30") (pin "1") (pinfunction "1_1") (pintype "passive"))
    )
    (net (code "87") (name "Net-(P2-Pad39)") (class "Default")
      (node (ref "P2") (pin "39") (pinfunction "39_39") (pintype "passive"))
      (node (ref "R35") (pin "1") (pinfunction "1_1") (pintype "passive"))
    )
    (net (code "88") (name "Net-(P2-Pad40)") (class "Default")
      (node (ref "P2") (pin "40") (pinfunction "40_40") (pintype "passive"))
      (node (ref "R34") (pin "1") (pinfunction "1_1") (pintype "passive"))
    )
    (net (code "89") (name "Net-(P3-Pad1)") (class "Default")
      (node (ref "P3") (pin "1") (pinfunction "1_1") (pintype "passive"))
      (node (ref "R32") (pin "2") (pinfunction "2_2") (pintype "passive"))
    )
    (net (code "90") (name "Net-(P3-Pad2)") (class "Default")
      (node (ref "P3") (pin "2") (pinfunction "2_2") (pintype "passive"))
      (node (ref "R33") (pin "1") (pinfunction "1_1") (pintype "passive"))
    )
    (net (code "91") (name "Net-(U1-QA)") (class "Default")
      (node (ref "R1") (pin "2") (pinfunction "2_2") (pintype "passive"))
      (node (ref "U1") (pin "15") (pinfunction "QA_15") (pintype "tri_state"))
    )
    (net (code "92") (name "Net-(U1-QB)") (class "Default")
      (node (ref "R2") (pin "2") (pinfunction "2_2") (pintype "passive"))
      (node (ref "U1") (pin "1") (pinfunction "QB_1") (pintype "tri_state"))
    )
    (net (code "93") (name "Net-(U1-QC)") (class "Default")
      (node (ref "R3") (pin "2") (pinfunction "2_2") (pintype "passive"))
      (node (ref "U1") (pin "2") (pinfunction "QC_2") (pintype "tri_state"))
    )
    (net (code "94") (name "Net-(U1-QD)") (class "Default")
      (node (ref "R5") (pin "2") (pinfunction "2_2") (pintype "passive"))
      (node (ref "U1") (pin "3") (pinfunction "QD_3") (pintype "tri_state"))
    )
    (net (code "95") (name "Net-(U1-QE)") (class "Default")
      (node (ref "R6") (pin "2") (pinfunction "2_2") (pintype "passive"))
      (node (ref "U1") (pin "4") (pinfunction "QE_4") (pintype "tri_state"))
    )
    (net (code "96") (name "Net-(U1-QF)") (class "Default")
      (node (ref "R7") (pin "2") (pinfunction "2_2") (pintype "passive"))
      (node (ref "U1") (pin "5") (pinfunction "QF_5") (pintype "tri_state"))
    )
    (net (code "97") (name "Net-(U1-QG)") (class "Default")
      (node (ref "R8") (pin "2") (pinfunction "2_2") (pintype "passive"))
      (node (ref "U1") (pin "6") (pinfunction "QG_6") (pintype "tri_state"))
    )
    (net (code "98") (name "Net-(U1-QH)") (class "Default")
      (node (ref "R9") (pin "2") (pinfunction "2_2") (pintype "passive"))
      (node (ref "U1") (pin "7") (pinfunction "QH_7") (pintype "tri_state"))
    )
    (net (code "99") (name "Net-(U1-~{RST})") (class "Default")
      (node (ref "C2") (pin "2") (pinfunction "2_2") (pintype "passive"))
      (node (ref "R4") (pin "1") (pinfunction "1_1") (pintype "passive"))
      (node (ref "U1") (pin "10") (pinfunction "~{RST}_10") (pintype "input"))
    )
    (net (code "100") (name "Net-(U2-QA)") (class "Default")
      (node (ref "R10") (pin "2") (pinfunction "2_2") (pintype "passive"))
      (node (ref "U2") (pin "15") (pinfunction "QA_15") (pintype "tri_state"))
    )
    (net (code "101") (name "Net-(U2-QB)") (class "Default")
      (node (ref "R11") (pin "2") (pinfunction "2_2") (pintype "passive"))
      (node (ref "U2") (pin "1") (pinfunction "QB_1") (pintype "tri_state"))
    )
    (net (code "102") (name "Net-(U2-QC)") (class "Default")
      (node (ref "R12") (pin "2") (pinfunction "2_2") (pintype "passive"))
      (node (ref "U2") (pin "2") (pinfunction "QC_2") (pintype "tri_state"))
    )
    (net (code "103") (name "Net-(U2-QD)") (class "Default")
      (node (ref "R14") (pin "2") (pinfunction "2_2") (pintype "passive"))
      (node (ref "U2") (pin "3") (pinfunction "QD_3") (pintype "tri_state"))
    )
    (net (code "104") (name "Net-(U2-QE)") (class "Default")
      (node (ref "R15") (pin "2") (pinfunction "2_2") (pintype "passive"))
      (node (ref "U2") (pin "4") (pinfunction "QE_4") (pintype "tri_state"))
    )
    (net (code "105") (name "Net-(U2-QF)") (class "Default")
      (node (ref "R16") (pin "2") (pinfunction "2_2") (pintype "passive"))
      (node (ref "U2") (pin "5") (pinfunction "QF_5") (pintype "tri_state"))
    )
    (net (code "106") (name "Net-(U2-QG)") (class "Default")
      (node (ref "R17") (pin "2") (pinfunction "2_2") (pintype "passive"))
      (node (ref "U2") (pin "6") (pinfunction "QG_6") (pintype "tri_state"))
    )
    (net (code "107") (name "Net-(U2-QH)") (class "Default")
      (node (ref "R18") (pin "2") (pinfunction "2_2") (pintype "passive"))
      (node (ref "U2") (pin "7") (pinfunction "QH_7") (pintype "tri_state"))
    )
    (net (code "108") (name "Net-(U2-~{RST})") (class "Default")
      (node (ref "C4") (pin "2") (pinfunction "2_2") (pintype "passive"))
      (node (ref "R13") (pin "1") (pinfunction "1_1") (pintype "passive"))
      (node (ref "U2") (pin "10") (pinfunction "~{RST}_10") (pintype "input"))
    )
    (net (code "109") (name "Net-(U3-QA)") (class "Default")
      (node (ref "R19") (pin "2") (pinfunction "2_2") (pintype "passive"))
      (node (ref "U3") (pin "15") (pinfunction "QA_15") (pintype "tri_state"))
    )
    (net (code "110") (name "Net-(U3-QB)") (class "Default")
      (node (ref "R20") (pin "2") (pinfunction "2_2") (pintype "passive"))
      (node (ref "U3") (pin "1") (pinfunction "QB_1") (pintype "tri_state"))
    )
    (net (code "111") (name "Net-(U3-QC)") (class "Default")
      (node (ref "R21") (pin "2") (pinfunction "2_2") (pintype "passive"))
      (node (ref "U3") (pin "2") (pinfunction "QC_2") (pintype "tri_state"))
    )
    (net (code "112") (name "Net-(U3-QD)") (class "Default")
      (node (ref "R23") (pin "2") (pinfunction "2_2") (pintype "passive"))
      (node (ref "U3") (pin "3") (pinfunction "QD_3") (pintype "tri_state"))
    )
    (net (code "113") (name "Net-(U3-QE)") (class "Default")
      (node (ref "R24") (pin "2") (pinfunction "2_2") (pintype "passive"))
      (node (ref "U3") (pin "4") (pinfunction "QE_4") (pintype "tri_state"))
    )
    (net (code "114") (name "Net-(U3-QF)") (class "Default")
      (node (ref "R25") (pin "2") (pinfunction "2_2") (pintype "passive"))
      (node (ref "U3") (pin "5") (pinfunction "QF_5") (pintype "tri_state"))
    )
    (net (code "115") (name "Net-(U3-QG)") (class "Default")
      (node (ref "R26") (pin "2") (pinfunction "2_2") (pintype "passive"))
      (node (ref "U3") (pin "6") (pinfunction "QG_6") (pintype "tri_state"))
    )
    (net (code "116") (name "Net-(U3-QH)") (class "Default")
      (node (ref "R27") (pin "2") (pinfunction "2_2") (pintype "passive"))
      (node (ref "U3") (pin "7") (pinfunction "QH_7") (pintype "tri_state"))
    )
    (net (code "117") (name "Net-(U3-~{RST})") (class "Default")
      (node (ref "C6") (pin "2") (pinfunction "2_2") (pintype "passive"))
      (node (ref "R22") (pin "1") (pinfunction "1_1") (pintype "passive"))
      (node (ref "U3") (pin "10") (pinfunction "~{RST}_10") (pintype "input"))
    )
    (net (code "118") (name "Net-(U4-QA)") (class "Default")
      (node (ref "R28") (pin "2") (pinfunction "2_2") (pintype "passive"))
      (node (ref "U4") (pin "15") (pinfunction "QA_15") (pintype "tri_state"))
    )
    (net (code "119") (name "Net-(U4-QB)") (class "Default")
      (node (ref "R29") (pin "2") (pinfunction "2_2") (pintype "passive"))
      (node (ref "U4") (pin "1") (pinfunction "QB_1") (pintype "tri_state"))
    )
    (net (code "120") (name "Net-(U4-QC)") (class "Default")
      (node (ref "R30") (pin "2") (pinfunction "2_2") (pintype "passive"))
      (node (ref "U4") (pin "2") (pinfunction "QC_2") (pintype "tri_state"))
    )
    (net (code "121") (name "Net-(U4-QD)") (class "Default")
      (node (ref "R34") (pin "2") (pinfunction "2_2") (pintype "passive"))
      (node (ref "U4") (pin "3") (pinfunction "QD_3") (pintype "tri_state"))
    )
    (net (code "122") (name "Net-(U4-QE)") (class "Default")
      (node (ref "R35") (pin "2") (pinfunction "2_2") (pintype "passive"))
      (node (ref "U4") (pin "4") (pinfunction "QE_4") (pintype "tri_state"))
    )
    (net (code "123") (name "Net-(U4-QF)") (class "Default")
      (node (ref "R36") (pin "2") (pinfunction "2_2") (pintype "passive"))
      (node (ref "U4") (pin "5") (pinfunction "QF_5") (pintype "tri_state"))
    )
    (net (code "124") (name "Net-(U4-QG)") (class "Default")
      (node (ref "R37") (pin "2") (pinfunction "2_2") (pintype "passive"))
      (node (ref "U4") (pin "6") (pinfunction "QG_6") (pintype "tri_state"))
    )
    (net (code "125") (name "Net-(U4-QH)") (class "Default")
      (node (ref "R38") (pin "2") (pinfunction "2_2") (pintype "passive"))
      (node (ref "U4") (pin "7") (pinfunction "QH_7") (pintype "tri_state"))
    )
    (net (code "126") (name "Net-(U4-~{RST})") (class "Default")
      (node (ref "C8") (pin "2") (pinfunction "2_2") (pintype "passive"))
      (node (ref "R31") (pin "1") (pinfunction "1_1") (pintype "passive"))
      (node (ref "U4") (pin "10") (pinfunction "~{RST}_10") (pintype "input"))
    )
    (net (code "127") (name "Net-(U5-QA)") (class "Default")
      (node (ref "R39") (pin "2") (pinfunction "2_2") (pintype "passive"))
      (node (ref "U5") (pin "15") (pinfunction "QA_15") (pintype "tri_state"))
    )
    (net (code "128") (name "Net-(U5-QB)") (class "Default")
      (node (ref "R40") (pin "2") (pinfunction "2_2") (pintype "passive"))
      (node (ref "U5") (pin "1") (pinfunction "QB_1") (pintype "tri_state"))
    )
    (net (code "129") (name "Net-(U5-QC)") (class "Default")
      (node (ref "R41") (pin "2") (pinfunction "2_2") (pintype "passive"))
      (node (ref "U5") (pin "2") (pinfunction "QC_2") (pintype "tri_state"))
    )
    (net (code "130") (name "Net-(U5-QD)") (class "Default")
      (node (ref "R43") (pin "2") (pinfunction "2_2") (pintype "passive"))
      (node (ref "U5") (pin "3") (pinfunction "QD_3") (pintype "tri_state"))
    )
    (net (code "131") (name "Net-(U5-QE)") (class "Default")
      (node (ref "R44") (pin "2") (pinfunction "2_2") (pintype "passive"))
      (node (ref "U5") (pin "4") (pinfunction "QE_4") (pintype "tri_state"))
    )
    (net (code "132") (name "Net-(U5-QF)") (class "Default")
      (node (ref "R45") (pin "2") (pinfunction "2_2") (pintype "passive"))
      (node (ref "U5") (pin "5") (pinfunction "QF_5") (pintype "tri_state"))
    )
    (net (code "133") (name "Net-(U5-QG)") (class "Default")
      (node (ref "R46") (pin "2") (pinfunction "2_2") (pintype "passive"))
      (node (ref "U5") (pin "6") (pinfunction "QG_6") (pintype "tri_state"))
    )
    (net (code "134") (name "Net-(U5-QH)") (class "Default")
      (node (ref "R47") (pin "2") (pinfunction "2_2") (pintype "passive"))
      (node (ref "U5") (pin "7") (pinfunction "QH_7") (pintype "tri_state"))
    )
    (net (code "135") (name "Net-(U5-~{RST})") (class "Default")
      (node (ref "C10") (pin "2") (pinfunction "2_2") (pintype "passive"))
      (node (ref "R42") (pin "1") (pinfunction "1_1") (pintype "passive"))
      (node (ref "U5") (pin "10") (pinfunction "~{RST}_10") (pintype "input"))
    )
    (net (code "136") (name "VSS_SKC") (class "Default")
      (node (ref "C1") (pin "2") (pinfunction "2_2") (pintype "passive"))
      (node (ref "C10") (pin "1") (pinfunction "1_1") (pintype "passive"))
      (node (ref "C2") (pin "1") (pinfunction "1_1") (pintype "passive"))
      (node (ref "C3") (pin "2") (pinfunction "2_2") (pintype "passive"))
      (node (ref "C4") (pin "1") (pinfunction "1_1") (pintype "passive"))
      (node (ref "C5") (pin "2") (pinfunction "2_2") (pintype "passive"))
      (node (ref "C6") (pin "1") (pinfunction "1_1") (pintype "passive"))
      (node (ref "C7") (pin "2") (pinfunction "2_2") (pintype "passive"))
      (node (ref "C8") (pin "1") (pinfunction "1_1") (pintype "passive"))
      (node (ref "C9") (pin "2") (pinfunction "2_2") (pintype "passive"))
      (node (ref "R32") (pin "1") (pinfunction "1_1") (pintype "passive"))
      (node (ref "R33") (pin "2") (pinfunction "2_2") (pintype "passive"))
      (node (ref "U1") (pin "13") (pinfunction "~{OE}_13") (pintype "input"))
      (node (ref "U1") (pin "8") (pinfunction "GND_8") (pintype "power_in"))
      (node (ref "U2") (pin "13") (pinfunction "~{OE}_13") (pintype "input"))
      (node (ref "U2") (pin "8") (pinfunction "GND_8") (pintype "power_in"))
      (node (ref "U3") (pin "13") (pinfunction "~{OE}_13") (pintype "input"))
      (node (ref "U3") (pin "8") (pinfunction "GND_8") (pintype "power_in"))
      (node (ref "U4") (pin "13") (pinfunction "~{OE}_13") (pintype "input"))
      (node (ref "U4") (pin "8") (pinfunction "GND_8") (pintype "power_in"))
      (node (ref "U5") (pin "13") (pinfunction "~{OE}_13") (pintype "input"))
      (node (ref "U5") (pin "8") (pinfunction "GND_8") (pintype "power_in"))
    )
    (net (code "137") (name "unconnected-(U1-SDO-Pad9)") (class "Default")
      (node (ref "U1") (pin "9") (pinfunction "SDO_9") (pintype "output"))
    )
    (net (code "138") (name "unconnected-(U2-SDO-Pad9)") (class "Default")
      (node (ref "U2") (pin "9") (pinfunction "SDO_9") (pintype "output"))
    )
    (net (code "139") (name "unconnected-(U3-SDO-Pad9)") (class "Default")
      (node (ref "U3") (pin "9") (pinfunction "SDO_9") (pintype "output"))
    )
    (net (code "140") (name "unconnected-(U4-SDO-Pad9)") (class "Default")
      (node (ref "U4") (pin "9") (pinfunction "SDO_9") (pintype "output"))
    )
    (net (code "141") (name "unconnected-(U5-SDO-Pad9)") (class "Default")
      (node (ref "U5") (pin "9") (pinfunction "SDO_9") (pintype "output"))
    )
  )
)
